# Sheet1.net
KiCad netlist of a schematic drawn in Altium Designer
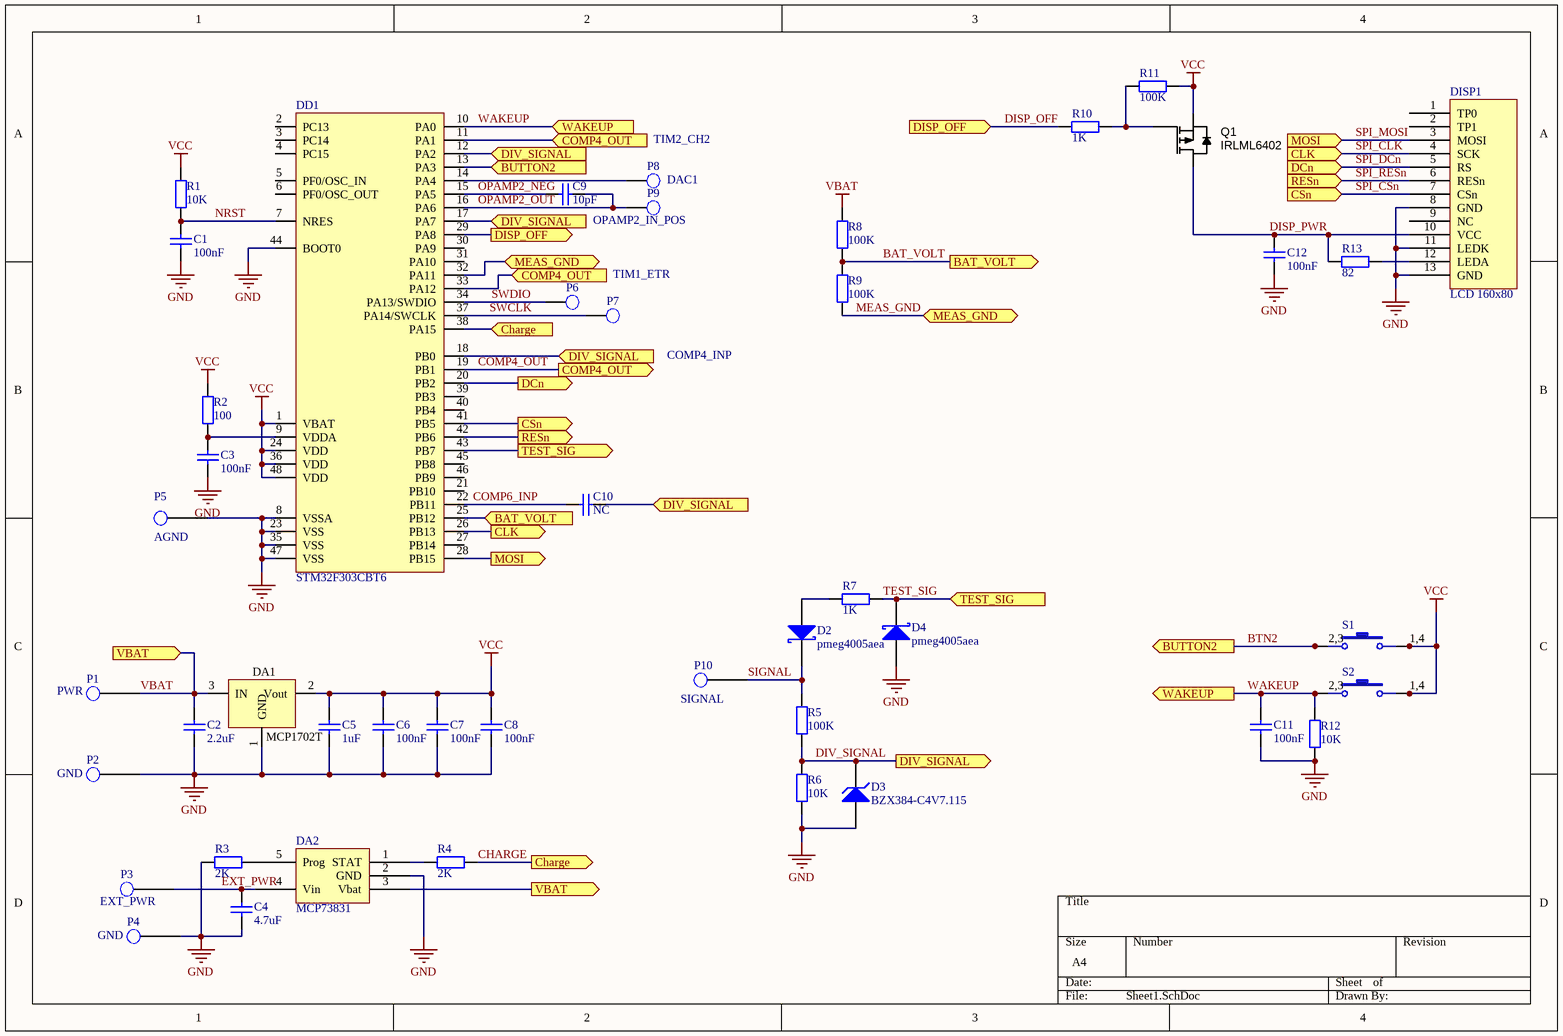
[diagram p0: Sheet1.SchDoc]

(export (version "E")
  (design (tool "Eeschema 10.0.6"))
  (components
    (comp (ref "C1")
      (value "100nF")
      (footprint "CAPC1608X90N")
      (description "Chip capacitor")
      (fields (field (name "VOLTAGE") "25V"))
      (libsource (lib "MyLibSch") (part "CC0805"))
    )
    (comp (ref "C2")
      (value "2.2uF")
      (footprint "CAPC2012X135N")
      (description "Chip capacitor")
      (fields (field (name "VOLTAGE") "25V"))
      (libsource (lib "MyLibSch") (part "CC0805"))
    )
    (comp (ref "C3")
      (value "100nF")
      (footprint "CAPC1608X90N")
      (description "Chip capacitor")
      (fields (field (name "VOLTAGE") "25V"))
      (libsource (lib "MyLibSch") (part "CC0805"))
    )
    (comp (ref "C4")
      (value "4.7uF")
      (footprint "CAPC2012X135N")
      (description "Chip capacitor")
      (fields (field (name "VOLTAGE") "25V"))
      (libsource (lib "MyLibSch") (part "CC0805"))
    )
    (comp (ref "C5")
      (value "1uF")
      (footprint "CAPC2012X135N")
      (description "Chip capacitor")
      (fields (field (name "VOLTAGE") "25V"))
      (libsource (lib "MyLibSch") (part "CC0805"))
    )
    (comp (ref "C6")
      (value "100nF")
      (footprint "CAPC1608X90N")
      (description "Chip capacitor")
      (fields (field (name "VOLTAGE") "25V"))
      (libsource (lib "MyLibSch") (part "CC0805"))
    )
    (comp (ref "C7")
      (value "100nF")
      (footprint "CAPC1608X90N")
      (description "Chip capacitor")
      (fields (field (name "VOLTAGE") "25V"))
      (libsource (lib "MyLibSch") (part "CC0805"))
    )
    (comp (ref "C8")
      (value "100nF")
      (footprint "CAPC1608X90N")
      (description "Chip capacitor")
      (fields (field (name "VOLTAGE") "25V"))
      (libsource (lib "MyLibSch") (part "CC0805"))
    )
    (comp (ref "C9")
      (value "10pF")
      (footprint "CAPC1608X90N")
      (description "Chip capacitor")
      (fields (field (name "VOLTAGE") "25V"))
      (libsource (lib "MyLibSch") (part "CC0805"))
    )
    (comp (ref "C10")
      (value "NC")
      (footprint "CAPC1608X90N")
      (description "Chip capacitor")
      (fields (field (name "VOLTAGE") "25V"))
      (libsource (lib "MyLibSch") (part "CC0805"))
    )
    (comp (ref "C11")
      (value "100nF")
      (footprint "CAPC1608X90N")
      (description "Chip capacitor")
      (fields (field (name "VOLTAGE") "25V"))
      (libsource (lib "MyLibSch") (part "CC0805"))
    )
    (comp (ref "C12")
      (value "100nF")
      (footprint "CAPC1608X90N")
      (description "Chip capacitor")
      (fields (field (name "VOLTAGE") "25V"))
      (libsource (lib "MyLibSch") (part "CC0805"))
    )
    (comp (ref "D2")
      (value "pmeg4005aea")
      (footprint "SOD-323F/SC-90_INV")
      (description "Schottky Diode")
      (fields (field (name "PUBLISHER") "Altium Limited"))
      (libsource (lib "Miscellaneous Devices") (part "D Schottky"))
    )
    (comp (ref "D3")
      (value "BZX384-C4V7.115")
      (footprint "SOD-323F/SC-90_INV")
      (description "Zener Diode")
      (fields (field (name "PUBLISHER") "Altium Limited"))
      (libsource (lib "Miscellaneous Devices") (part "D Zener"))
    )
    (comp (ref "D4")
      (value "pmeg4005aea")
      (footprint "SOD-323F/SC-90_INV")
      (description "Schottky Diode")
      (fields (field (name "PUBLISHER") "Altium Limited"))
      (libsource (lib "Miscellaneous Devices") (part "D Schottky"))
    )
    (comp (ref "DA1")
      (value "MCP1702T")
      (footprint "SOT23-3")
      (description "Linear voltage regulator")
      (libsource (lib "lcd_lib") (part "MCP1702T"))
    )
    (comp (ref "DA2")
      (value "MCP73831")
      (footprint "SOT23-5")
      (description "Li-Ion Charger")
      (libsource (lib "lcd_lib") (part "MCP73831"))
    )
    (comp (ref "DD1")
      (value "STM32F303CBT6")
      (footprint "LQFP-48_N")
      (description "Microcontroller")
      (libsource (lib "lcd_lib") (part "STM32F3_LQFP48"))
    )
    (comp (ref "DISP1")
      (value "LCD 160x80")
      (footprint "LCD_160_80")
      (libsource (lib "lcd_lib") (part "LCD_160x80"))
    )
    (comp (ref "P1")
      (value "PWR")
      (footprint "Ext_pad_2")
      (description "Pad for wire")
      (libsource (lib "lcd_lib") (part "Ext Pad"))
    )
    (comp (ref "P2")
      (value "GND")
      (footprint "Ext_pad_2")
      (description "Pad for wire")
      (libsource (lib "lcd_lib") (part "Ext Pad"))
    )
    (comp (ref "P3")
      (value "EXT_PWR")
      (footprint "Ext_pad_2")
      (description "Pad for wire")
      (libsource (lib "lcd_lib") (part "Ext Pad"))
    )
    (comp (ref "P4")
      (value "GND")
      (footprint "Ext_pad_2")
      (description "Pad for wire")
      (libsource (lib "lcd_lib") (part "Ext Pad"))
    )
    (comp (ref "P5")
      (value "AGND")
      (footprint "PcbLib3:Ext_hole")
      (description "Hole Pad")
      (libsource (lib "lcd_lib") (part "Hole Pad"))
    )
    (comp (ref "P6")
      (value "Pad")
      (footprint "PcbLib3:Ext_pad_2")
      (description "Pad for wire")
      (libsource (lib "") (part "Ext Pad_1"))
    )
    (comp (ref "P7")
      (value "Pad")
      (footprint "PcbLib3:Ext_pad_2")
      (description "Pad for wire")
      (libsource (lib "") (part "Ext Pad_1"))
    )
    (comp (ref "P8")
      (value "DAC1")
      (footprint "Ext_pad_small")
      (description "Pad for wire")
      (libsource (lib "") (part "Ext Pad_1"))
    )
    (comp (ref "P9")
      (value "Pad")
      (footprint "Ext_pad_small")
      (description "Pad for wire")
      (libsource (lib "") (part "Ext Pad_1"))
    )
    (comp (ref "P10")
      (value "SIGNAL")
      (footprint "Ext_pad")
      (description "Pad for wire")
      (libsource (lib "lcd_lib") (part "Ext Pad"))
    )
    (comp (ref "Q1")
      (value "IRLML6402")
      (footprint "SOT23-3")
      (description "MOSFET SMD P-CH")
      (libsource (lib "PBL - Transistors") (part "MOSFET_RZR025P01TL"))
    )
    (comp (ref "R1")
      (value "10K")
      (footprint "RESC1608X55N")
      (description "Chip resistor")
      (fields (field (name "TOLERANCE") "5%"))
      (libsource (lib "MyLibSch") (part "RC0805"))
    )
    (comp (ref "R2")
      (value "100")
      (footprint "RESC1608X55N")
      (description "Chip resistor")
      (fields (field (name "TOLERANCE") "5%"))
      (libsource (lib "") (part "RC0805_2"))
    )
    (comp (ref "R3")
      (value "2K")
      (footprint "RESC1608X55N")
      (description "Chip resistor")
      (fields (field (name "TOLERANCE") "5%"))
      (libsource (lib "MyLibSch") (part "RC0805"))
    )
    (comp (ref "R4")
      (value "2K")
      (footprint "RESC1608X55N")
      (description "Chip resistor")
      (fields (field (name "TOLERANCE") "5%"))
      (libsource (lib "") (part "RC0805_3"))
    )
    (comp (ref "R5")
      (value "100K")
      (footprint "RESC1608X55N")
      (description "Chip resistor")
      (fields (field (name "TOLERANCE") "5%"))
      (libsource (lib "MyLibSch") (part "RC0805"))
    )
    (comp (ref "R6")
      (value "10K")
      (footprint "RESC1608X55N")
      (description "Chip resistor")
      (fields (field (name "TOLERANCE") "5%"))
      (libsource (lib "MyLibSch") (part "RC0805"))
    )
    (comp (ref "R7")
      (value "1K")
      (footprint "RESC1608X55N")
      (description "Chip resistor")
      (fields (field (name "TOLERANCE") "5%"))
      (libsource (lib "") (part "RC0805_1"))
    )
    (comp (ref "R8")
      (value "100K")
      (footprint "RESC1608X55N")
      (description "Chip resistor")
      (fields (field (name "TOLERANCE") "5%"))
      (libsource (lib "MyLibSch") (part "RC0805"))
    )
    (comp (ref "R9")
      (value "100K")
      (footprint "RESC1608X55N")
      (description "Chip resistor")
      (fields (field (name "TOLERANCE") "5%"))
      (libsource (lib "MyLibSch") (part "RC0805"))
    )
    (comp (ref "R10")
      (value "1K")
      (footprint "RESC1608X55N")
      (description "Chip resistor")
      (fields (field (name "TOLERANCE") "5%"))
      (libsource (lib "") (part "RC0805_1"))
    )
    (comp (ref "R11")
      (value "100K")
      (footprint "RESC1608X55N")
      (description "Chip resistor")
      (fields (field (name "TOLERANCE") "5%"))
      (libsource (lib "") (part "RC0805_1"))
    )
    (comp (ref "R12")
      (value "10K")
      (footprint "RESC1608X55N")
      (description "Chip resistor")
      (fields (field (name "TOLERANCE") "5%"))
      (libsource (lib "MyLibSch") (part "RC0805"))
    )
    (comp (ref "R13")
      (value "82")
      (footprint "RESC1608X55N")
      (description "Chip resistor")
      (fields (field (name "TOLERANCE") "5%"))
      (libsource (lib "") (part "RC0805_1"))
    )
    (comp (ref "S1")
      (value "SWT-6")
      (footprint "BUTTON_B3FS")
      (description "Switch")
      (libsource (lib "MyLibSch") (part "SWT-6"))
    )
    (comp (ref "S2")
      (value "SWT-6")
      (footprint "BUTTON_B3FS")
      (description "Switch")
      (libsource (lib "MyLibSch") (part "SWT-6"))
    )
  )
  (nets
    (net (code "1") (name "/BAT_VOLT") (class "Default")
      (node (ref "DD1") (pin "25") (pinfunction "PB12_25") (pintype "passive"))
      (node (ref "R8") (pin "2") (pinfunction "2_2") (pintype "passive"))
      (node (ref "R9") (pin "1") (pinfunction "1_1") (pintype "passive"))
    )
    (net (code "2") (name "/BTN2") (class "Default")
      (node (ref "DD1") (pin "13") (pinfunction "PA3_13") (pintype "passive"))
      (node (ref "S1") (pin "2") (pinfunction "2_2") (pintype "passive"))
      (node (ref "S1") (pin "3") (pinfunction "3_3") (pintype "passive"))
    )
    (net (code "3") (name "/CHARGE") (class "Default")
      (node (ref "DD1") (pin "38") (pinfunction "PA15_38") (pintype "passive"))
      (node (ref "R4") (pin "1") (pinfunction "1_1") (pintype "passive"))
    )
    (net (code "4") (name "/COMP4_OUT") (class "Default")
      (node (ref "DD1") (pin "11") (pinfunction "PA1_11") (pintype "passive"))
      (node (ref "DD1") (pin "19") (pinfunction "PB1_19") (pintype "passive"))
      (node (ref "DD1") (pin "33") (pinfunction "PA12_33") (pintype "passive"))
    )
    (net (code "5") (name "/COMP6_INP") (class "Default")
      (node (ref "C10") (pin "2") (pinfunction "2_2") (pintype "passive"))
      (node (ref "DD1") (pin "22") (pinfunction "PB11_22") (pintype "passive"))
    )
    (net (code "6") (name "/DISP_OFF") (class "Default")
      (node (ref "DD1") (pin "29") (pinfunction "PA8_29") (pintype "passive"))
      (node (ref "R10") (pin "1") (pinfunction "1_1") (pintype "passive"))
    )
    (net (code "7") (name "/DISP_PWR") (class "Default")
      (node (ref "C12") (pin "1") (pinfunction "1_1") (pintype "passive"))
      (node (ref "DISP1") (pin "10") (pinfunction "VCC_10") (pintype "passive"))
      (node (ref "Q1") (pin "3") (pinfunction "D_3") (pintype "passive"))
      (node (ref "R13") (pin "1") (pinfunction "1_1") (pintype "passive"))
    )
    (net (code "8") (name "/DIV_SIGNAL") (class "Default")
      (node (ref "C10") (pin "1") (pinfunction "1_1") (pintype "passive"))
      (node (ref "D3") (pin "2") (pinfunction "K_2") (pintype "passive"))
      (node (ref "DD1") (pin "12") (pinfunction "PA2_12") (pintype "passive"))
      (node (ref "DD1") (pin "17") (pinfunction "PA7_17") (pintype "passive"))
      (node (ref "DD1") (pin "18") (pinfunction "PB0_18") (pintype "passive"))
      (node (ref "R5") (pin "2") (pinfunction "2_2") (pintype "passive"))
      (node (ref "R6") (pin "1") (pinfunction "1_1") (pintype "passive"))
    )
    (net (code "9") (name "/EXT_PWR") (class "Default")
      (node (ref "C4") (pin "2") (pinfunction "2_2") (pintype "passive"))
      (node (ref "DA2") (pin "4") (pinfunction "Vin_4") (pintype "power_in"))
      (node (ref "P3") (pin "1") (pinfunction "Pad_1") (pintype "passive"))
    )
    (net (code "10") (name "/MEAS_GND") (class "Default")
      (node (ref "DD1") (pin "32") (pinfunction "PA11_32") (pintype "passive"))
      (node (ref "R9") (pin "2") (pinfunction "2_2") (pintype "passive"))
    )
    (net (code "11") (name "/NRST") (class "Default")
      (node (ref "C1") (pin "2") (pinfunction "2_2") (pintype "passive"))
      (node (ref "DD1") (pin "7") (pinfunction "NRES_7") (pintype "passive"))
      (node (ref "R1") (pin "2") (pinfunction "2_2") (pintype "passive"))
    )
    (net (code "12") (name "/OPAMP2_NEG") (class "Default")
      (node (ref "C9") (pin "2") (pinfunction "2_2") (pintype "passive"))
      (node (ref "DD1") (pin "15") (pinfunction "PA5_15") (pintype "passive"))
    )
    (net (code "13") (name "/OPAMP2_OUT") (class "Default")
      (node (ref "C9") (pin "1") (pinfunction "1_1") (pintype "passive"))
      (node (ref "DD1") (pin "16") (pinfunction "PA6_16") (pintype "passive"))
      (node (ref "P9") (pin "1") (pinfunction "Pad_1") (pintype "passive"))
    )
    (net (code "14") (name "/SIGNAL") (class "Default")
      (node (ref "D2") (pin "2") (pinfunction "K_2") (pintype "passive"))
      (node (ref "P10") (pin "1") (pinfunction "Pad_1") (pintype "passive"))
      (node (ref "R5") (pin "1") (pinfunction "1_1") (pintype "passive"))
    )
    (net (code "15") (name "/SPI_CLK") (class "Default")
      (node (ref "DD1") (pin "26") (pinfunction "PB13_26") (pintype "passive"))
      (node (ref "DISP1") (pin "4") (pinfunction "SCK_4") (pintype "passive"))
    )
    (net (code "16") (name "/SPI_CSn") (class "Default")
      (node (ref "DD1") (pin "41") (pinfunction "PB5_41") (pintype "passive"))
      (node (ref "DISP1") (pin "7") (pinfunction "CSn_7") (pintype "passive"))
    )
    (net (code "17") (name "/SPI_DCn") (class "Default")
      (node (ref "DD1") (pin "20") (pinfunction "PB2_20") (pintype "passive"))
      (node (ref "DISP1") (pin "5") (pinfunction "RS_5") (pintype "passive"))
    )
    (net (code "18") (name "/SPI_MOSI") (class "Default")
      (node (ref "DD1") (pin "28") (pinfunction "PB15_28") (pintype "passive"))
      (node (ref "DISP1") (pin "3") (pinfunction "MOSI_3") (pintype "passive"))
    )
    (net (code "19") (name "/SPI_RESn") (class "Default")
      (node (ref "DD1") (pin "42") (pinfunction "PB6_42") (pintype "passive"))
      (node (ref "DISP1") (pin "6") (pinfunction "RESn_6") (pintype "passive"))
    )
    (net (code "20") (name "/SWCLK") (class "Default")
      (node (ref "DD1") (pin "37") (pinfunction "PA14/SWCLK_37") (pintype "passive"))
      (node (ref "P7") (pin "1") (pinfunction "Pad_1") (pintype "passive"))
    )
    (net (code "21") (name "/SWDIO") (class "Default")
      (node (ref "DD1") (pin "34") (pinfunction "PA13/SWDIO_34") (pintype "passive"))
      (node (ref "P6") (pin "1") (pinfunction "Pad_1") (pintype "passive"))
    )
    (net (code "22") (name "/TEST_SIG") (class "Default")
      (node (ref "D4") (pin "2") (pinfunction "K_2") (pintype "passive"))
      (node (ref "DD1") (pin "43") (pinfunction "PB7_43") (pintype "passive"))
      (node (ref "R7") (pin "2") (pinfunction "2_2") (pintype "passive"))
    )
    (net (code "23") (name "/WAKEUP") (class "Default")
      (node (ref "C11") (pin "1") (pinfunction "1_1") (pintype "passive"))
      (node (ref "DD1") (pin "10") (pinfunction "PA0_10") (pintype "passive"))
      (node (ref "R12") (pin "1") (pinfunction "1_1") (pintype "passive"))
      (node (ref "S2") (pin "2") (pinfunction "2_2") (pintype "passive"))
      (node (ref "S2") (pin "3") (pinfunction "3_3") (pintype "passive"))
    )
    (net (code "24") (name "GND") (class "Default")
      (node (ref "C1") (pin "1") (pinfunction "1_1") (pintype "passive"))
      (node (ref "C11") (pin "2") (pinfunction "2_2") (pintype "passive"))
      (node (ref "C12") (pin "2") (pinfunction "2_2") (pintype "passive"))
      (node (ref "C2") (pin "2") (pinfunction "2_2") (pintype "passive"))
      (node (ref "C3") (pin "1") (pinfunction "1_1") (pintype "passive"))
      (node (ref "C4") (pin "1") (pinfunction "1_1") (pintype "passive"))
      (node (ref "C5") (pin "1") (pinfunction "1_1") (pintype "passive"))
      (node (ref "C6") (pin "1") (pinfunction "1_1") (pintype "passive"))
      (node (ref "C7") (pin "1") (pinfunction "1_1") (pintype "passive"))
      (node (ref "C8") (pin "1") (pinfunction "1_1") (pintype "passive"))
      (node (ref "D3") (pin "1") (pinfunction "A_1") (pintype "passive"))
      (node (ref "D4") (pin "1") (pinfunction "A_1") (pintype "passive"))
      (node (ref "DA1") (pin "1") (pinfunction "GND_1") (pintype "power_in"))
      (node (ref "DA2") (pin "2") (pinfunction "GND_2") (pintype "power_in"))
      (node (ref "DD1") (pin "23") (pinfunction "VSS_23") (pintype "passive"))
      (node (ref "DD1") (pin "35") (pinfunction "VSS_35") (pintype "passive"))
      (node (ref "DD1") (pin "44") (pinfunction "BOOT0_44") (pintype "passive"))
      (node (ref "DD1") (pin "47") (pinfunction "VSS_47") (pintype "passive"))
      (node (ref "DD1") (pin "8") (pinfunction "VSSA_8") (pintype "passive"))
      (node (ref "DISP1") (pin "11") (pinfunction "LEDK_11") (pintype "passive"))
      (node (ref "DISP1") (pin "13") (pinfunction "GND_13") (pintype "passive"))
      (node (ref "DISP1") (pin "8") (pinfunction "GND_8") (pintype "passive"))
      (node (ref "P2") (pin "1") (pinfunction "Pad_1") (pintype "passive"))
      (node (ref "P4") (pin "1") (pinfunction "Pad_1") (pintype "passive"))
      (node (ref "P5") (pin "1") (pinfunction "Pad_1") (pintype "passive"))
      (node (ref "R12") (pin "2") (pinfunction "2_2") (pintype "passive"))
      (node (ref "R3") (pin "2") (pinfunction "2_2") (pintype "passive"))
      (node (ref "R6") (pin "2") (pinfunction "2_2") (pintype "passive"))
    )
    (net (code "25") (name "Net-(D2-A)") (class "Default")
      (node (ref "D2") (pin "1") (pinfunction "A_1") (pintype "passive"))
      (node (ref "R7") (pin "1") (pinfunction "1_1") (pintype "passive"))
    )
    (net (code "26") (name "Net-(DA2-Prog)") (class "Default")
      (node (ref "DA2") (pin "5") (pinfunction "Prog_5") (pintype "passive"))
      (node (ref "R3") (pin "1") (pinfunction "1_1") (pintype "passive"))
    )
    (net (code "27") (name "Net-(DA2-STAT)") (class "Default")
      (node (ref "DA2") (pin "1") (pinfunction "STAT_1") (pintype "open_collector"))
      (node (ref "R4") (pin "2") (pinfunction "2_2") (pintype "passive"))
    )
    (net (code "28") (name "Net-(DD1-PA4)") (class "Default")
      (node (ref "DD1") (pin "14") (pinfunction "PA4_14") (pintype "passive"))
      (node (ref "P8") (pin "1") (pinfunction "Pad_1") (pintype "passive"))
    )
    (net (code "29") (name "Net-(DD1-VDDA)") (class "Default")
      (node (ref "C3") (pin "2") (pinfunction "2_2") (pintype "passive"))
      (node (ref "DD1") (pin "9") (pinfunction "VDDA_9") (pintype "passive"))
      (node (ref "R2") (pin "1") (pinfunction "1_1") (pintype "passive"))
    )
    (net (code "30") (name "Net-(DISP1-LEDA)") (class "Default")
      (node (ref "DISP1") (pin "12") (pinfunction "LEDA_12") (pintype "passive"))
      (node (ref "R13") (pin "2") (pinfunction "2_2") (pintype "passive"))
    )
    (net (code "31") (name "Net-(Q1-G)") (class "Default")
      (node (ref "Q1") (pin "1") (pinfunction "G_1") (pintype "passive"))
      (node (ref "R10") (pin "2") (pinfunction "2_2") (pintype "passive"))
      (node (ref "R11") (pin "1") (pinfunction "1_1") (pintype "passive"))
    )
    (net (code "32") (name "VBAT") (class "Default")
      (node (ref "C2") (pin "1") (pinfunction "1_1") (pintype "passive"))
      (node (ref "DA1") (pin "3") (pinfunction "IN_3") (pintype "power_in"))
      (node (ref "DA2") (pin "3") (pinfunction "Vbat_3") (pintype "power_in"))
      (node (ref "P1") (pin "1") (pinfunction "Pad_1") (pintype "passive"))
      (node (ref "R8") (pin "1") (pinfunction "1_1") (pintype "passive"))
    )
    (net (code "33") (name "VCC") (class "Default")
      (node (ref "C5") (pin "2") (pinfunction "2_2") (pintype "passive"))
      (node (ref "C6") (pin "2") (pinfunction "2_2") (pintype "passive"))
      (node (ref "C7") (pin "2") (pinfunction "2_2") (pintype "passive"))
      (node (ref "C8") (pin "2") (pinfunction "2_2") (pintype "passive"))
      (node (ref "DA1") (pin "2") (pinfunction "Vout_2") (pintype "power_in"))
      (node (ref "DD1") (pin "1") (pinfunction "VBAT_1") (pintype "passive"))
      (node (ref "DD1") (pin "24") (pinfunction "VDD_24") (pintype "passive"))
      (node (ref "DD1") (pin "36") (pinfunction "VDD_36") (pintype "passive"))
      (node (ref "DD1") (pin "48") (pinfunction "VDD_48") (pintype "passive"))
      (node (ref "Q1") (pin "2") (pinfunction "S_2") (pintype "passive"))
      (node (ref "R1") (pin "1") (pinfunction "1_1") (pintype "passive"))
      (node (ref "R11") (pin "2") (pinfunction "2_2") (pintype "passive"))
      (node (ref "R2") (pin "2") (pinfunction "2_2") (pintype "passive"))
      (node (ref "S1") (pin "1") (pinfunction "1_1") (pintype "passive"))
      (node (ref "S1") (pin "4") (pinfunction "4_4") (pintype "passive"))
      (node (ref "S2") (pin "1") (pinfunction "1_1") (pintype "passive"))
      (node (ref "S2") (pin "4") (pinfunction "4_4") (pintype "passive"))
    )
    (net (code "34") (name "unconnected-(DD1-PA9-Pad30)") (class "Default")
      (node (ref "DD1") (pin "30") (pinfunction "PA9_30") (pintype "passive"))
    )
    (net (code "35") (name "unconnected-(DD1-PA10-Pad31)") (class "Default")
      (node (ref "DD1") (pin "31") (pinfunction "PA10_31") (pintype "passive"))
    )
    (net (code "36") (name "unconnected-(DD1-PB3-Pad39)") (class "Default")
      (node (ref "DD1") (pin "39") (pinfunction "PB3_39") (pintype "passive"))
    )
    (net (code "37") (name "unconnected-(DD1-PB4-Pad40)") (class "Default")
      (node (ref "DD1") (pin "40") (pinfunction "PB4_40") (pintype "passive"))
    )
    (net (code "38") (name "unconnected-(DD1-PB8-Pad45)") (class "Default")
      (node (ref "DD1") (pin "45") (pinfunction "PB8_45") (pintype "passive"))
    )
    (net (code "39") (name "unconnected-(DD1-PB9-Pad46)") (class "Default")
      (node (ref "DD1") (pin "46") (pinfunction "PB9_46") (pintype "passive"))
    )
    (net (code "40") (name "unconnected-(DD1-PB10-Pad21)") (class "Default")
      (node (ref "DD1") (pin "21") (pinfunction "PB10_21") (pintype "passive"))
    )
    (net (code "41") (name "unconnected-(DD1-PB14-Pad27)") (class "Default")
      (node (ref "DD1") (pin "27") (pinfunction "PB14_27") (pintype "passive"))
    )
    (net (code "42") (name "unconnected-(DD1-PC13-Pad2)") (class "Default")
      (node (ref "DD1") (pin "2") (pinfunction "PC13_2") (pintype "passive"))
    )
    (net (code "43") (name "unconnected-(DD1-PC14-Pad3)") (class "Default")
      (node (ref "DD1") (pin "3") (pinfunction "PC14_3") (pintype "passive"))
    )
    (net (code "44") (name "unconnected-(DD1-PC15-Pad4)") (class "Default")
      (node (ref "DD1") (pin "4") (pinfunction "PC15_4") (pintype "passive"))
    )
    (net (code "45") (name "unconnected-(DD1-PF0{slash}OSC_IN-Pad5)") (class "Default")
      (node (ref "DD1") (pin "5") (pinfunction "PF0/OSC_IN_5") (pintype "passive"))
    )
    (net (code "46") (name "unconnected-(DD1-PF0{slash}OSC_OUT-Pad6)") (class "Default")
      (node (ref "DD1") (pin "6") (pinfunction "PF0/OSC_OUT_6") (pintype "passive"))
    )
    (net (code "47") (name "unconnected-(DISP1-NC-Pad9)") (class "Default")
      (node (ref "DISP1") (pin "9") (pinfunction "NC_9") (pintype "passive"))
    )
    (net (code "48") (name "unconnected-(DISP1-TP0-Pad1)") (class "Default")
      (node (ref "DISP1") (pin "1") (pinfunction "TP0_1") (pintype "passive"))
    )
    (net (code "49") (name "unconnected-(DISP1-TP1-Pad2)") (class "Default")
      (node (ref "DISP1") (pin "2") (pinfunction "TP1_2") (pintype "passive"))
    )
  )
)
